# 15_-_BOOT_OPTIONS.net
KiCad netlist of a schematic drawn in Altium Designer
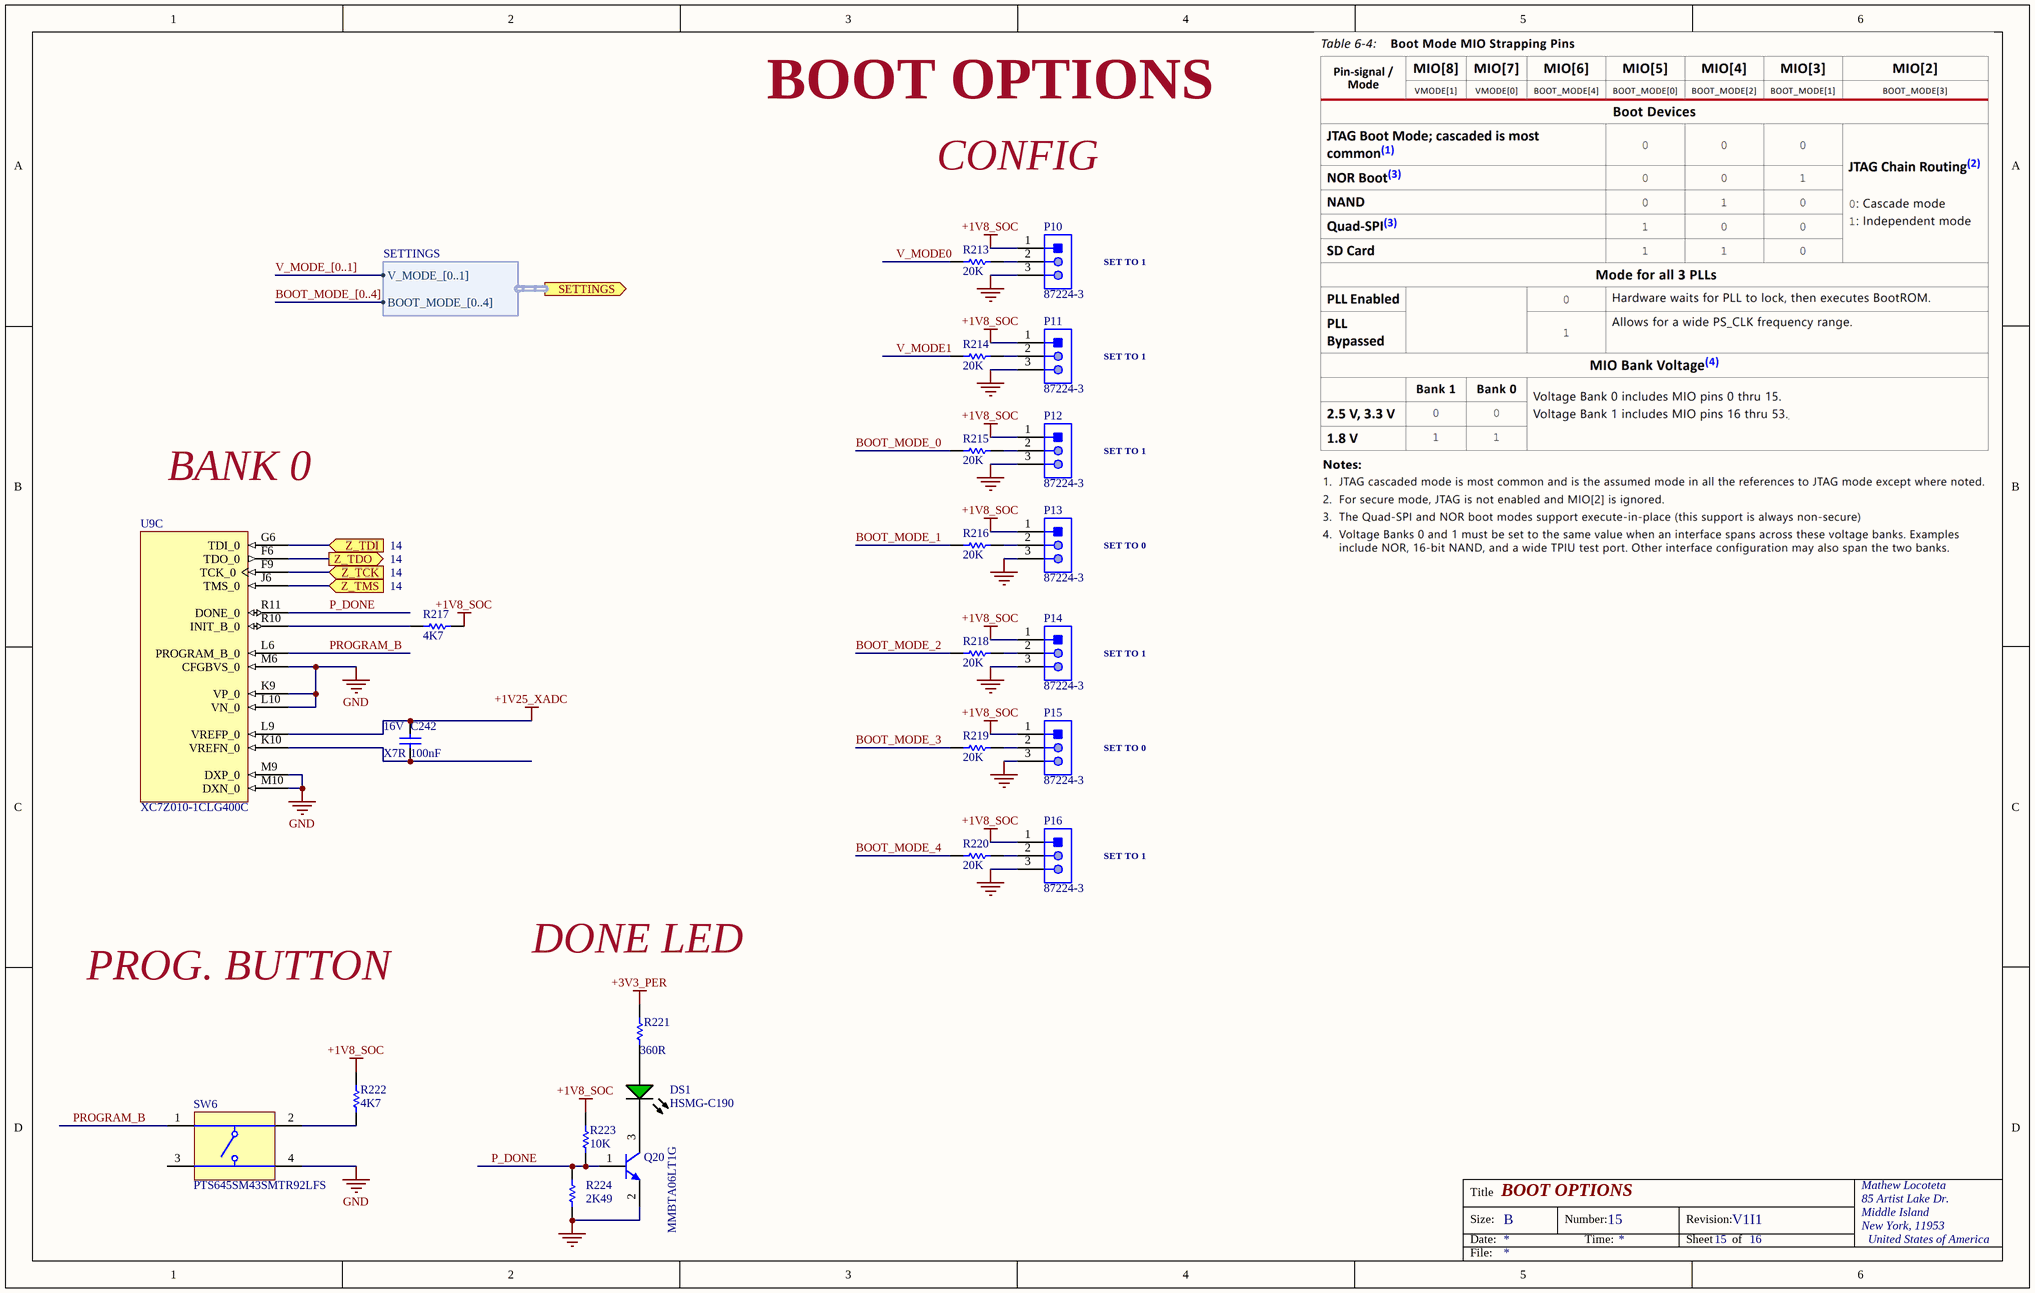
[diagram p0: [15] - BOOT OPTIONS.SchDoc]

(export (version "E")
  (design (tool "Eeschema 10.0.6"))
  (components
    (comp (ref "C242")
      (value "100nF 0402 16V")
      (fields
        (field (name "MANUFACTURER") "KEMET")
        (field (name "MANUFACTURER PART NUMBER") "C0402C104J4RACTU")
        (field (name "TOLERANCE") "5%")
        (field (name "DIELECTRIC") "X7R")
        (field (name "VOLTAGE RATING") "16V")
        (field (name "CAPACITANCE") "100nF")
      )
      (libsource (lib "Zynq 7000") (part "C0402C104J4RACTU"))
    )
    (comp (ref "DS1")
      (value "HSMG-C190")
      (footprint "AVAG-HSMX-C190_V")
      (description "Chip LED, Green, 2.2 V, -40 to 85 degC, 2-Pin SMD, RoHS, Tape and Reel")
      (libsource (lib "Altium Content Vault") (part "LED-GREEN-AK-2"))
    )
    (comp (ref "P10")
      (value "87224-3")
      (footprint "TECO-87224-3_V")
      (fields (field (name "MANUFACTURER") "TE Connectivity"))
      (libsource (lib "Altium Content Vault") (part "CN-1P-M-R3"))
    )
    (comp (ref "P11")
      (value "87224-3")
      (footprint "TECO-87224-3_V")
      (fields (field (name "MANUFACTURER") "TE Connectivity"))
      (libsource (lib "Altium Content Vault") (part "CN-1P-M-R3"))
    )
    (comp (ref "P12")
      (value "87224-3")
      (footprint "TECO-87224-3_V")
      (fields (field (name "MANUFACTURER") "TE Connectivity"))
      (libsource (lib "Altium Content Vault") (part "CN-1P-M-R3"))
    )
    (comp (ref "P13")
      (value "87224-3")
      (footprint "TECO-87224-3_V")
      (fields (field (name "MANUFACTURER") "TE Connectivity"))
      (libsource (lib "Altium Content Vault") (part "CN-1P-M-R3"))
    )
    (comp (ref "P14")
      (value "87224-3")
      (footprint "TECO-87224-3_V")
      (fields (field (name "MANUFACTURER") "TE Connectivity"))
      (libsource (lib "Altium Content Vault") (part "CN-1P-M-R3"))
    )
    (comp (ref "P15")
      (value "87224-3")
      (footprint "TECO-87224-3_V")
      (fields (field (name "MANUFACTURER") "TE Connectivity"))
      (libsource (lib "Altium Content Vault") (part "CN-1P-M-R3"))
    )
    (comp (ref "P16")
      (value "87224-3")
      (footprint "TECO-87224-3_V")
      (fields (field (name "MANUFACTURER") "TE Connectivity"))
      (libsource (lib "Altium Content Vault") (part "CN-1P-M-R3"))
    )
    (comp (ref "Q20")
      (value "MMBTA06LT1G")
      (footprint "ONSC-SOT-23-3-318-08_V")
      (description "Driver Transistor, NPN Silicon, 3-Pin SOT-23, Pb-Free, Tape and Reel")
      (fields (field (name "MANUFACTURER") "On Semiconductor"))
      (libsource (lib "Altium Content Vault") (part "ONSC-NPN-B1E2C3-3"))
    )
    (comp (ref "R213")
      (value "20K 1/8W 1% 0402")
      (description "Res Thick Film 0402 20K Ohm 1% 1/8W 100ppm/C Molded SMD SMD Paper T/R")
      (fields
        (field (name "MANUFACTURER") "Vishay Dale")
        (field (name "MANUFACTURER PART NUMBER") "CRCW040220K0FKEDHP")
        (field (name "RESISTANCE") "20K")
      )
      (libsource (lib "Zynq 7000") (part "CRCW040220K0FKEDHP"))
    )
    (comp (ref "R214")
      (value "20K 1/8W 1% 0402")
      (description "Res Thick Film 0402 20K Ohm 1% 1/8W 100ppm/C Molded SMD SMD Paper T/R")
      (fields
        (field (name "MANUFACTURER") "Vishay Dale")
        (field (name "MANUFACTURER PART NUMBER") "CRCW040220K0FKEDHP")
        (field (name "RESISTANCE") "20K")
      )
      (libsource (lib "Zynq 7000") (part "CRCW040220K0FKEDHP"))
    )
    (comp (ref "R215")
      (value "20K 1/8W 1% 0402")
      (description "Res Thick Film 0402 20K Ohm 1% 1/8W 100ppm/C Molded SMD SMD Paper T/R")
      (fields
        (field (name "MANUFACTURER") "Vishay Dale")
        (field (name "MANUFACTURER PART NUMBER") "CRCW040220K0FKEDHP")
        (field (name "RESISTANCE") "20K")
      )
      (libsource (lib "Zynq 7000") (part "CRCW040220K0FKEDHP"))
    )
    (comp (ref "R216")
      (value "20K 1/8W 1% 0402")
      (description "Res Thick Film 0402 20K Ohm 1% 1/8W 100ppm/C Molded SMD SMD Paper T/R")
      (fields
        (field (name "MANUFACTURER") "Vishay Dale")
        (field (name "MANUFACTURER PART NUMBER") "CRCW040220K0FKEDHP")
        (field (name "RESISTANCE") "20K")
      )
      (libsource (lib "Zynq 7000") (part "CRCW040220K0FKEDHP"))
    )
    (comp (ref "R217")
      (value "4K7 0402 1%")
      (description "Resistor SMD 4.7 kOhm 0402 PU=10000 ST, CRCW04024K70FKED, Vishay")
      (fields
        (field (name "MANUFACTURER") "Vishay")
        (field (name "MANUFACTURER PART NUMBER") "CRCW04024K70FKED")
        (field (name "RESISTANCE") "4K7")
      )
      (libsource (lib "Zynq 7000") (part "CRCW04024K70FKED"))
    )
    (comp (ref "R218")
      (value "20K 1/8W 1% 0402")
      (description "Res Thick Film 0402 20K Ohm 1% 1/8W 100ppm/C Molded SMD SMD Paper T/R")
      (fields
        (field (name "MANUFACTURER") "Vishay Dale")
        (field (name "MANUFACTURER PART NUMBER") "CRCW040220K0FKEDHP")
        (field (name "RESISTANCE") "20K")
      )
      (libsource (lib "Zynq 7000") (part "CRCW040220K0FKEDHP"))
    )
    (comp (ref "R219")
      (value "20K 1/8W 1% 0402")
      (description "Res Thick Film 0402 20K Ohm 1% 1/8W 100ppm/C Molded SMD SMD Paper T/R")
      (fields
        (field (name "MANUFACTURER") "Vishay Dale")
        (field (name "MANUFACTURER PART NUMBER") "CRCW040220K0FKEDHP")
        (field (name "RESISTANCE") "20K")
      )
      (libsource (lib "Zynq 7000") (part "CRCW040220K0FKEDHP"))
    )
    (comp (ref "R220")
      (value "20K 1/8W 1% 0402")
      (description "Res Thick Film 0402 20K Ohm 1% 1/8W 100ppm/C Molded SMD SMD Paper T/R")
      (fields
        (field (name "MANUFACTURER") "Vishay Dale")
        (field (name "MANUFACTURER PART NUMBER") "CRCW040220K0FKEDHP")
        (field (name "RESISTANCE") "20K")
      )
      (libsource (lib "Zynq 7000") (part "CRCW040220K0FKEDHP"))
    )
    (comp (ref "R221")
      (value "360R")
      (footprint "RESC1005X40X25NL05T05")
      (fields (field (name "PART NUMBER") "CRCW0402360RFKED") (field (name "MANUFACTURER") "Vishay Dale"))
      (libsource (lib "Altium Content Vault") (part "RES"))
    )
    (comp (ref "R222")
      (value "4K7 0402 1%")
      (description "Resistor SMD 4.7 kOhm 0402 PU=10000 ST, CRCW04024K70FKED, Vishay")
      (fields
        (field (name "MANUFACTURER") "Vishay")
        (field (name "MANUFACTURER PART NUMBER") "CRCW04024K70FKED")
        (field (name "RESISTANCE") "4K7")
      )
      (libsource (lib "Zynq 7000") (part "CRCW04024K70FKED"))
    )
    (comp (ref "R223")
      (value "10K")
      (footprint "RESC1005X40X25ML05T10")
      (fields (field (name "PART NUMBER") "CRCW040210K0FKEDHP") (field (name "MANUFACTURER") "Vishay Dale"))
      (libsource (lib "Altium Content Vault") (part "RES"))
    )
    (comp (ref "R224")
      (value "2K49")
      (footprint "RESC1005X40X25ML05T05")
      (fields (field (name "MANUFACTURER") "Vishay Dale") (field (name "PART NUMBER") "CRCW04022K49FKTD"))
      (libsource (lib "Altium Content Vault") (part "RES"))
    )
    (comp (ref "SW6")
      (value "PTS645SM43SMTR92LFS")
      (footprint "ITT-PTS645S-4_V")
      (description "6 mm Tact Switche, SPST, NO, -20 to 60 degC, 4-Pin SMT, RoHS, Tape and Reel")
      (fields (field (name "MANUFACTURER") "ITT Cannon"))
      (libsource (lib "Altium Content Vault") (part "SW-SPST-4_A"))
    )
    (comp (ref "U9")
      (value "XC7Z010-1CLG400C")
      (footprint "CLG400")
      (fields (field (name "GENERIC PART NUMBER") "XC7Z010"))
      (libsource (lib "Altium Content Vault") (part "XNLX-XC7Z010-CLG400"))
    )
  )
  (nets
    (net (code "4") (name "+1V8_SOC") (class "Default")
      (node (ref "P10") (pin "1") (pinfunction "1_1") (pintype "passive"))
      (node (ref "P11") (pin "1") (pinfunction "1_1") (pintype "passive"))
      (node (ref "P12") (pin "1") (pinfunction "1_1") (pintype "passive"))
      (node (ref "P13") (pin "1") (pinfunction "1_1") (pintype "passive"))
      (node (ref "P14") (pin "1") (pinfunction "1_1") (pintype "passive"))
      (node (ref "P15") (pin "1") (pinfunction "1_1") (pintype "passive"))
      (node (ref "P16") (pin "1") (pinfunction "1_1") (pintype "passive"))
      (node (ref "R217") (pin "2") (pinfunction "2_2") (pintype "passive"))
      (node (ref "R222") (pin "1") (pinfunction "1_1") (pintype "passive"))
      (node (ref "R223") (pin "2") (pinfunction "2_2") (pintype "passive"))
    )
    (net (code "5") (name "+1V25_XADC") (class "Default")
      (node (ref "C242") (pin "2") (pinfunction "2_2") (pintype "passive"))
      (node (ref "U9") (pin "L9") (pinfunction "VREFP_0_L9") (pintype "input"))
    )
    (net (code "6") (name "+3V3_PER") (class "Default")
      (node (ref "R221") (pin "2") (pinfunction "2_2") (pintype "passive"))
    )
    (net (code "7") (name "/BOOT_MODE_0") (class "Default")
      (node (ref "R215") (pin "1") (pinfunction "1_1") (pintype "passive"))
    )
    (net (code "8") (name "/BOOT_MODE_1") (class "Default")
      (node (ref "R216") (pin "1") (pinfunction "1_1") (pintype "passive"))
    )
    (net (code "9") (name "/BOOT_MODE_2") (class "Default")
      (node (ref "R218") (pin "1") (pinfunction "1_1") (pintype "passive"))
    )
    (net (code "10") (name "/BOOT_MODE_3") (class "Default")
      (node (ref "R219") (pin "1") (pinfunction "1_1") (pintype "passive"))
    )
    (net (code "11") (name "/BOOT_MODE_4") (class "Default")
      (node (ref "R220") (pin "1") (pinfunction "1_1") (pintype "passive"))
    )
    (net (code "13") (name "/PROGRAM_B") (class "Default")
      (node (ref "SW6") (pin "1") (pinfunction "1_1") (pintype "passive"))
      (node (ref "U9") (pin "L6") (pinfunction "PROGRAM_B_0_L6") (pintype "input"))
    )
    (net (code "14") (name "/P_DONE") (class "Default")
      (node (ref "Q20") (pin "1") (pinfunction "B_1") (pintype "passive"))
      (node (ref "R223") (pin "1") (pinfunction "1_1") (pintype "passive"))
      (node (ref "R224") (pin "2") (pinfunction "2_2") (pintype "passive"))
      (node (ref "U9") (pin "R11") (pinfunction "DONE_0_R11") (pintype "bidirectional"))
    )
    (net (code "15") (name "/V_MODE0") (class "Default")
      (node (ref "R213") (pin "1") (pinfunction "1_1") (pintype "passive"))
    )
    (net (code "16") (name "/V_MODE1") (class "Default")
      (node (ref "R214") (pin "1") (pinfunction "1_1") (pintype "passive"))
    )
    (net (code "18") (name "/Z_TCK") (class "Default")
      (node (ref "U9") (pin "F9") (pinfunction "TCK_0_F9") (pintype "input"))
    )
    (net (code "19") (name "/Z_TDI") (class "Default")
      (node (ref "U9") (pin "G6") (pinfunction "TDI_0_G6") (pintype "input"))
    )
    (net (code "20") (name "/Z_TDO") (class "Default")
      (node (ref "U9") (pin "F6") (pinfunction "TDO_0_F6") (pintype "output"))
    )
    (net (code "21") (name "/Z_TMS") (class "Default")
      (node (ref "U9") (pin "J6") (pinfunction "TMS_0_J6") (pintype "input"))
    )
    (net (code "23") (name "GND") (class "Default")
      (node (ref "P10") (pin "3") (pinfunction "3_3") (pintype "passive"))
      (node (ref "P11") (pin "3") (pinfunction "3_3") (pintype "passive"))
      (node (ref "P12") (pin "3") (pinfunction "3_3") (pintype "passive"))
      (node (ref "P13") (pin "3") (pinfunction "3_3") (pintype "passive"))
      (node (ref "P14") (pin "3") (pinfunction "3_3") (pintype "passive"))
      (node (ref "P15") (pin "3") (pinfunction "3_3") (pintype "passive"))
      (node (ref "P16") (pin "3") (pinfunction "3_3") (pintype "passive"))
      (node (ref "Q20") (pin "2") (pinfunction "E_2") (pintype "passive"))
      (node (ref "R224") (pin "1") (pinfunction "1_1") (pintype "passive"))
      (node (ref "SW6") (pin "4") (pinfunction "4_4") (pintype "passive"))
      (node (ref "U9") (pin "K9") (pinfunction "VP_0_K9") (pintype "input"))
      (node (ref "U9") (pin "L10") (pinfunction "VN_0_L10") (pintype "input"))
      (node (ref "U9") (pin "M10") (pinfunction "DXN_0_M10") (pintype "input"))
      (node (ref "U9") (pin "M6") (pinfunction "CFGBVS_0_M6") (pintype "input"))
      (node (ref "U9") (pin "M9") (pinfunction "DXP_0_M9") (pintype "input"))
    )
    (net (code "24") (name "Net-(DS1-A)") (class "Default")
      (node (ref "DS1") (pin "1") (pinfunction "A_1") (pintype "passive"))
      (node (ref "R221") (pin "1") (pinfunction "1_1") (pintype "passive"))
    )
    (net (code "25") (name "Net-(DS1-K)") (class "Default")
      (node (ref "DS1") (pin "2") (pinfunction "K_2") (pintype "passive"))
      (node (ref "Q20") (pin "3") (pinfunction "C_3") (pintype "passive"))
    )
    (net (code "26") (name "Net-(P10-Pad2)") (class "Default")
      (node (ref "P10") (pin "2") (pinfunction "2_2") (pintype "passive"))
      (node (ref "R213") (pin "2") (pinfunction "2_2") (pintype "passive"))
    )
    (net (code "27") (name "Net-(P11-Pad2)") (class "Default")
      (node (ref "P11") (pin "2") (pinfunction "2_2") (pintype "passive"))
      (node (ref "R214") (pin "2") (pinfunction "2_2") (pintype "passive"))
    )
    (net (code "28") (name "Net-(P12-Pad2)") (class "Default")
      (node (ref "P12") (pin "2") (pinfunction "2_2") (pintype "passive"))
      (node (ref "R215") (pin "2") (pinfunction "2_2") (pintype "passive"))
    )
    (net (code "29") (name "Net-(P13-Pad2)") (class "Default")
      (node (ref "P13") (pin "2") (pinfunction "2_2") (pintype "passive"))
      (node (ref "R216") (pin "2") (pinfunction "2_2") (pintype "passive"))
    )
    (net (code "30") (name "Net-(P14-Pad2)") (class "Default")
      (node (ref "P14") (pin "2") (pinfunction "2_2") (pintype "passive"))
      (node (ref "R218") (pin "2") (pinfunction "2_2") (pintype "passive"))
    )
    (net (code "31") (name "Net-(P15-Pad2)") (class "Default")
      (node (ref "P15") (pin "2") (pinfunction "2_2") (pintype "passive"))
      (node (ref "R219") (pin "2") (pinfunction "2_2") (pintype "passive"))
    )
    (net (code "32") (name "Net-(P16-Pad2)") (class "Default")
      (node (ref "P16") (pin "2") (pinfunction "2_2") (pintype "passive"))
      (node (ref "R220") (pin "2") (pinfunction "2_2") (pintype "passive"))
    )
    (net (code "33") (name "Net-(R222-Pad2)") (class "Default")
      (node (ref "R222") (pin "2") (pinfunction "2_2") (pintype "passive"))
      (node (ref "SW6") (pin "2") (pinfunction "2_2") (pintype "passive"))
    )
    (net (code "34") (name "Net-(U9C-INIT_B_0)") (class "Default")
      (node (ref "R217") (pin "1") (pinfunction "1_1") (pintype "passive"))
      (node (ref "U9") (pin "R10") (pinfunction "INIT_B_0_R10") (pintype "bidirectional"))
    )
    (net (code "35") (name "Net-(U9C-VREFN_0)") (class "Default")
      (node (ref "C242") (pin "1") (pinfunction "1_1") (pintype "passive"))
      (node (ref "U9") (pin "K10") (pinfunction "VREFN_0_K10") (pintype "input"))
    )
    (net (code "36") (name "unconnected-(SW6-Pad3)") (class "Default")
      (node (ref "SW6") (pin "3") (pinfunction "3_3") (pintype "passive"))
    )
  )
)
